# eps_bb.net
KiCad netlist of a schematic drawn in Altium Designer
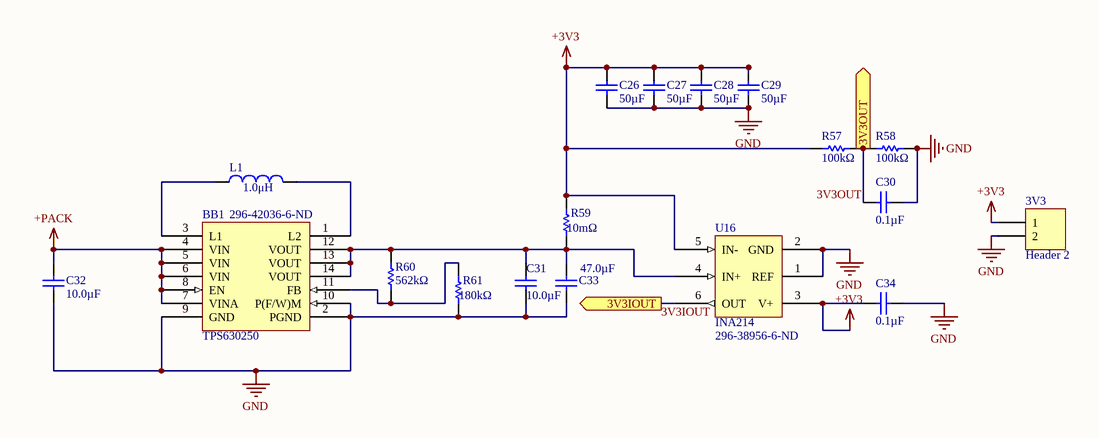
[diagram p0: eps_bb.SchDoc]

(export (version "E")
  (design (tool "Eeschema 10.0.6"))
  (components
    (comp (ref "3V3")
      (value "Header 2")
      (footprint "CON2_SCREW_5.00MM_691102710002")
      (description "Battery Header, 2-Pin")
      (fields (field (name "PUBLISHER") "Altium Limited"))
      (libsource (lib "Miscellaneous Connectors") (part "Header 2"))
    )
    (comp (ref "BB1")
      (value "TPS630250")
      (footprint "RNC0014A")
      (description "Buck-boost converter")
      (fields (field (name "SUPPLIER PART NUMBER 1") "296-42036-6-ND"))
      (libsource (lib "heron-general") (part "TPS630250"))
    )
    (comp (ref "C26")
      (value "50µF")
      (footprint "1608[0603]")
      (description "Capacitor")
      (fields (field (name "PUBLISHER") "Altium Limited"))
      (libsource (lib "Miscellaneous Devices") (part "Cap"))
    )
    (comp (ref "C27")
      (value "50µF")
      (footprint "1608[0603]")
      (description "Capacitor")
      (fields (field (name "PUBLISHER") "Altium Limited"))
      (libsource (lib "Miscellaneous Devices") (part "Cap"))
    )
    (comp (ref "C28")
      (value "50µF")
      (footprint "1608[0603]")
      (description "Capacitor")
      (fields (field (name "PUBLISHER") "Altium Limited"))
      (libsource (lib "Miscellaneous Devices") (part "Cap"))
    )
    (comp (ref "C29")
      (value "50µF")
      (footprint "1608[0603]")
      (description "Capacitor")
      (fields (field (name "PUBLISHER") "Altium Limited"))
      (libsource (lib "Miscellaneous Devices") (part "Cap"))
    )
    (comp (ref "C30")
      (value "0.1µF")
      (footprint "1608[0603]")
      (description "Capacitor")
      (fields (field (name "PUBLISHER") "Altium Limited"))
      (libsource (lib "Miscellaneous Devices") (part "Cap"))
    )
    (comp (ref "C31")
      (value "10.0µF")
      (footprint "1608[0603]")
      (description "Capacitor, Coutx")
      (fields (field (name "PUBLISHER") "Altium Limited"))
      (libsource (lib "Miscellaneous Devices") (part "Cap"))
    )
    (comp (ref "C32")
      (value "10.0µF")
      (footprint "1608[0603]")
      (description "Cin, capacitor")
      (fields (field (name "PUBLISHER") "Altium Limited"))
      (libsource (lib "Miscellaneous Devices") (part "Cap"))
    )
    (comp (ref "C33")
      (value "47.0µF")
      (footprint "1608[0603]")
      (description "Capacitor, Coutbb1")
      (fields (field (name "PUBLISHER") "Altium Limited"))
      (libsource (lib "Miscellaneous Devices") (part "Cap"))
    )
    (comp (ref "C34")
      (value "0.1µF")
      (footprint "1608[0603]")
      (description "Capacitor (Semiconductor SIM Model)")
      (fields (field (name "PUBLISHER") "Altium Limited"))
      (libsource (lib "Miscellaneous Devices") (part "Cap Semi"))
    )
    (comp (ref "L1")
      (value "1.0μH")
      (footprint "XAL4020-102ME")
      (description "Inductor, buck-boost")
      (fields (field (name "Comment") "Inductor") (field (name "PUBLISHER") "Altium Limited"))
      (libsource (lib "Miscellaneous Devices") (part "Inductor"))
    )
    (comp (ref "R57")
      (value "100kΩ")
      (footprint "1608[0603]")
      (description "Resistor")
      (fields (field (name "PUBLISHER") "Altium Limited"))
      (libsource (lib "Miscellaneous Devices") (part "Res1"))
    )
    (comp (ref "R58")
      (value "100kΩ")
      (footprint "1608[0603]")
      (description "Resistor")
      (fields (field (name "PUBLISHER") "Altium Limited"))
      (libsource (lib "Miscellaneous Devices") (part "Res1"))
    )
    (comp (ref "R59")
      (value "10mΩ")
      (footprint "C1206")
      (description "Resistor")
      (fields (field (name "Comment") "Res1") (field (name "PUBLISHER") "Altium Limited"))
      (libsource (lib "Miscellaneous Devices") (part "Res1"))
    )
    (comp (ref "R60")
      (value "562kΩ")
      (footprint "1608[0603]")
      (description "Resistor, Rfbt_bb1")
      (fields (field (name "PUBLISHER") "Altium Limited"))
      (libsource (lib "Miscellaneous Devices") (part "Res1"))
    )
    (comp (ref "R61")
      (value "180kΩ")
      (footprint "1608[0603]")
      (description "Resistor, Rfbb_bb1")
      (fields (field (name "PUBLISHER") "Altium Limited"))
      (libsource (lib "Miscellaneous Devices") (part "Res1"))
    )
    (comp (ref "U16")
      (value "INA214")
      (footprint "SOT65P210X110-6N")
      (description "Current monitor")
      (fields (field (name "SUPPLIER PART NUMBER 1") "296-38956-6-ND"))
      (libsource (lib "heron-general") (part "INA214"))
    )
  )
  (nets
    (net (code "1") (name "+3V3") (class "Default")
      (node (ref "3V3") (pin "1") (pinfunction "1_1") (pintype "passive"))
      (node (ref "C26") (pin "2") (pinfunction "2_2") (pintype "passive"))
      (node (ref "C27") (pin "2") (pinfunction "2_2") (pintype "passive"))
      (node (ref "C28") (pin "2") (pinfunction "2_2") (pintype "passive"))
      (node (ref "C29") (pin "2") (pinfunction "2_2") (pintype "passive"))
      (node (ref "C34") (pin "2") (pinfunction "2_2") (pintype "passive"))
      (node (ref "R57") (pin "1") (pinfunction "1_1") (pintype "passive"))
      (node (ref "R59") (pin "2") (pinfunction "2_2") (pintype "passive"))
      (node (ref "U16") (pin "3") (pinfunction "V+_3") (pintype "power_in"))
      (node (ref "U16") (pin "5") (pinfunction "IN-_5") (pintype "input"))
    )
    (net (code "2") (name "+PACK") (class "Default")
      (node (ref "BB1") (pin "4") (pinfunction "VIN_4") (pintype "power_in"))
      (node (ref "BB1") (pin "5") (pinfunction "VIN_5") (pintype "power_in"))
      (node (ref "BB1") (pin "6") (pinfunction "VIN_6") (pintype "power_in"))
      (node (ref "BB1") (pin "7") (pinfunction "VINA_7") (pintype "power_in"))
      (node (ref "BB1") (pin "8") (pinfunction "EN_8") (pintype "input"))
      (node (ref "C32") (pin "2") (pinfunction "2_2") (pintype "passive"))
    )
    (net (code "3") (name "/3V3IOUT") (class "Default")
      (node (ref "U16") (pin "6") (pinfunction "OUT_6") (pintype "output"))
    )
    (net (code "4") (name "/3V3OUT") (class "Default")
      (node (ref "C30") (pin "1") (pinfunction "1_1") (pintype "passive"))
      (node (ref "R57") (pin "2") (pinfunction "2_2") (pintype "passive"))
      (node (ref "R58") (pin "1") (pinfunction "1_1") (pintype "passive"))
    )
    (net (code "5") (name "GND") (class "Default")
      (node (ref "3V3") (pin "2") (pinfunction "2_2") (pintype "passive"))
      (node (ref "BB1") (pin "10") (pinfunction "P(F/W)M_10") (pintype "input"))
      (node (ref "BB1") (pin "2") (pinfunction "PGND_2") (pintype "power_in"))
      (node (ref "BB1") (pin "9") (pinfunction "GND_9") (pintype "power_in"))
      (node (ref "C26") (pin "1") (pinfunction "1_1") (pintype "passive"))
      (node (ref "C27") (pin "1") (pinfunction "1_1") (pintype "passive"))
      (node (ref "C28") (pin "1") (pinfunction "1_1") (pintype "passive"))
      (node (ref "C29") (pin "1") (pinfunction "1_1") (pintype "passive"))
      (node (ref "C30") (pin "2") (pinfunction "2_2") (pintype "passive"))
      (node (ref "C31") (pin "1") (pinfunction "1_1") (pintype "passive"))
      (node (ref "C32") (pin "1") (pinfunction "1_1") (pintype "passive"))
      (node (ref "C33") (pin "1") (pinfunction "1_1") (pintype "passive"))
      (node (ref "C34") (pin "1") (pinfunction "1_1") (pintype "passive"))
      (node (ref "R58") (pin "2") (pinfunction "2_2") (pintype "passive"))
      (node (ref "R61") (pin "1") (pinfunction "1_1") (pintype "passive"))
      (node (ref "U16") (pin "1") (pinfunction "REF_1") (pintype "passive"))
      (node (ref "U16") (pin "2") (pinfunction "GND_2") (pintype "power_in"))
    )
    (net (code "6") (name "Net-(BB1-FB)") (class "Default")
      (node (ref "BB1") (pin "11") (pinfunction "FB_11") (pintype "input"))
      (node (ref "R60") (pin "2") (pinfunction "2_2") (pintype "passive"))
      (node (ref "R61") (pin "2") (pinfunction "2_2") (pintype "passive"))
    )
    (net (code "7") (name "Net-(BB1-L1)") (class "Default")
      (node (ref "BB1") (pin "3") (pinfunction "L1_3") (pintype "power_in"))
      (node (ref "L1") (pin "1") (pinfunction "1_1") (pintype "passive"))
    )
    (net (code "8") (name "Net-(BB1-L2)") (class "Default")
      (node (ref "BB1") (pin "1") (pinfunction "L2_1") (pintype "power_in"))
      (node (ref "L1") (pin "2") (pinfunction "2_2") (pintype "passive"))
    )
    (net (code "9") (name "Net-(U16-IN+)") (class "Default")
      (node (ref "BB1") (pin "12") (pinfunction "VOUT_12") (pintype "passive"))
      (node (ref "BB1") (pin "13") (pinfunction "VOUT_13") (pintype "passive"))
      (node (ref "BB1") (pin "14") (pinfunction "VOUT_14") (pintype "passive"))
      (node (ref "C31") (pin "2") (pinfunction "2_2") (pintype "passive"))
      (node (ref "C33") (pin "2") (pinfunction "2_2") (pintype "passive"))
      (node (ref "R59") (pin "1") (pinfunction "1_1") (pintype "passive"))
      (node (ref "R60") (pin "1") (pinfunction "1_1") (pintype "passive"))
      (node (ref "U16") (pin "4") (pinfunction "IN+_4") (pintype "input"))
    )
  )
)
